# untitled.net
KiCad netlist of a schematic drawn in EAGLE
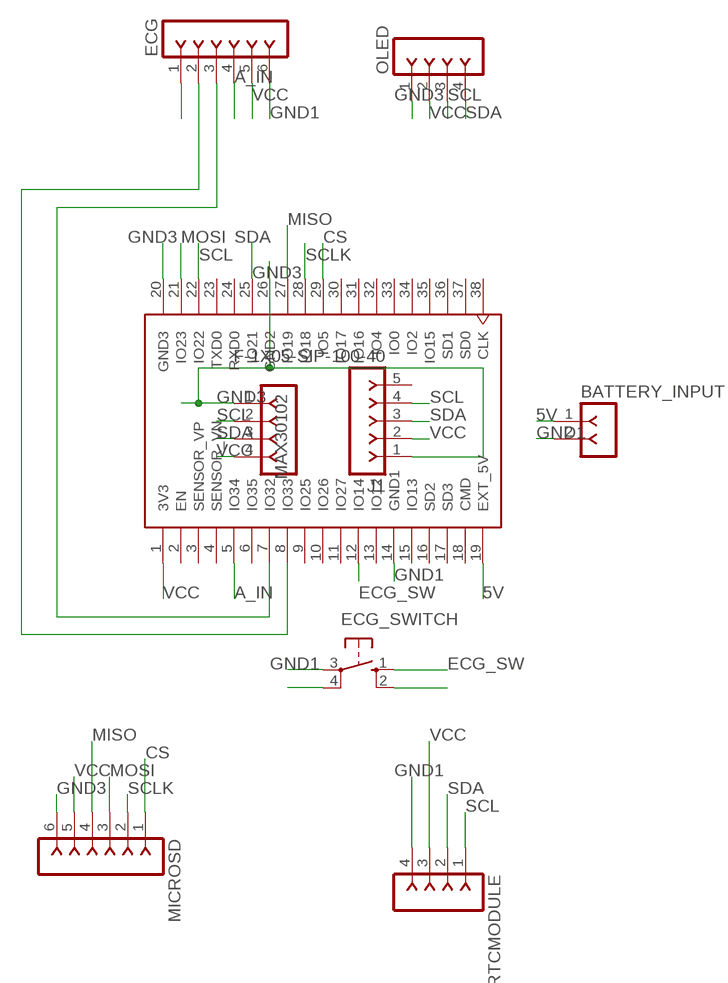
[diagram p0: schematic, sheet 1]

(export (version "E")
  (design (tool "Eeschema 10.0.6"))
  (components
    (comp (ref "BATTERY_INPUT")
      (value "F-1X02-SIP-100-40")
      (footprint "eagle-import:SIP-100-02-40")
      (libsource (lib "eagle-import") (part "F-1X02-SIP-100-40"))
    )
    (comp (ref "ECG")
      (value "F-1X06-SIP-100-40")
      (footprint "eagle-import:SIP-100-06-40")
      (libsource (lib "eagle-import") (part "F-1X06-SIP-100-40"))
    )
    (comp (ref "ECG_SWITCH")
      (value "10-XX")
      (footprint "eagle-import:B3F-10XX")
      (fields (field (name "MPN") "B3F-1000"))
      (libsource (lib "eagle-import") (part "10-XX"))
    )
    (comp (ref "J1")
      (value "F-1X05-SIP-100-40")
      (footprint "eagle-import:SIP-100-05-40")
      (libsource (lib "eagle-import") (part "F-1X05-SIP-100-40"))
    )
    (comp (ref "MAX30102")
      (value "F-1X04-SIP-100-40")
      (footprint "eagle-import:SIP-100-04-40")
      (libsource (lib "eagle-import") (part "F-1X04-SIP-100-40"))
    )
    (comp (ref "MICROSD")
      (value "F-1X06-SIP-100-40")
      (footprint "eagle-import:SIP-100-06-40")
      (libsource (lib "eagle-import") (part "F-1X06-SIP-100-40"))
    )
    (comp (ref "OLED")
      (value "F-1X04-SIP-100-40")
      (footprint "eagle-import:SIP-100-04-40")
      (libsource (lib "eagle-import") (part "F-1X04-SIP-100-40"))
    )
    (comp (ref "RTCMODULE")
      (value "F-1X04-SIP-100-40")
      (footprint "eagle-import:SIP-100-04-40")
      (libsource (lib "eagle-import") (part "F-1X04-SIP-100-40"))
    )
    (comp (ref "U1")
      (value "ESP32-DEVKITC-32D")
      (footprint "eagle-import:MODULE_ESP32-DEVKITC-32D")
      (fields (field (name "MF") "Espressif Systems"))
      (libsource (lib "eagle-import") (part "ESP32-DEVKITC-32D"))
    )
  )
  (nets
    (net (code "1") (name "/5V") (class "Default")
      (node (ref "BATTERY_INPUT") (pin "1") (pinfunction "1_1") (pintype "passive"))
      (node (ref "U1") (pin "19") (pinfunction "EXT_5V_19") (pintype "power_in"))
    )
    (net (code "2") (name "/A_IN") (class "Default")
      (node (ref "ECG") (pin "4") (pinfunction "4_4") (pintype "passive"))
      (node (ref "U1") (pin "5") (pinfunction "IO34_5") (pintype "bidirectional"))
    )
    (net (code "3") (name "/CS") (class "Default")
      (node (ref "MICROSD") (pin "1") (pinfunction "1_1") (pintype "passive"))
      (node (ref "U1") (pin "29") (pinfunction "IO5_29") (pintype "bidirectional"))
    )
    (net (code "4") (name "/ECG_SW") (class "Default")
      (node (ref "ECG_SWITCH") (pin "1") (pinfunction "S_1") (pintype "passive"))
      (node (ref "U1") (pin "12") (pinfunction "IO14_12") (pintype "bidirectional"))
    )
    (net (code "5") (name "/GND1") (class "Default")
      (node (ref "BATTERY_INPUT") (pin "2") (pinfunction "2_2") (pintype "passive"))
      (node (ref "ECG") (pin "6") (pinfunction "6_6") (pintype "passive"))
      (node (ref "ECG_SWITCH") (pin "3") (pinfunction "P_3") (pintype "passive"))
      (node (ref "RTCMODULE") (pin "4") (pinfunction "4_4") (pintype "passive"))
      (node (ref "U1") (pin "14") (pinfunction "GND1_14") (pintype "power_in"))
    )
    (net (code "6") (name "/GND3") (class "Default")
      (node (ref "J1") (pin "1") (pinfunction "1_1") (pintype "passive"))
      (node (ref "MAX30102") (pin "1") (pinfunction "1_1") (pintype "passive"))
      (node (ref "MICROSD") (pin "6") (pinfunction "6_6") (pintype "passive"))
      (node (ref "OLED") (pin "1") (pinfunction "1_1") (pintype "passive"))
      (node (ref "U1") (pin "20") (pinfunction "GND3_20") (pintype "power_in"))
      (node (ref "U1") (pin "26") (pinfunction "GND2_26") (pintype "power_in"))
    )
    (net (code "7") (name "/MISO") (class "Default")
      (node (ref "MICROSD") (pin "4") (pinfunction "4_4") (pintype "passive"))
      (node (ref "U1") (pin "27") (pinfunction "IO19_27") (pintype "bidirectional"))
    )
    (net (code "8") (name "/MOSI") (class "Default")
      (node (ref "MICROSD") (pin "3") (pinfunction "3_3") (pintype "passive"))
      (node (ref "U1") (pin "21") (pinfunction "IO23_21") (pintype "bidirectional"))
    )
    (net (code "9") (name "/SCL") (class "Default")
      (node (ref "J1") (pin "4") (pinfunction "4_4") (pintype "passive"))
      (node (ref "MAX30102") (pin "2") (pinfunction "2_2") (pintype "passive"))
      (node (ref "OLED") (pin "3") (pinfunction "3_3") (pintype "passive"))
      (node (ref "RTCMODULE") (pin "1") (pinfunction "1_1") (pintype "passive"))
      (node (ref "U1") (pin "22") (pinfunction "IO22_22") (pintype "bidirectional"))
    )
    (net (code "10") (name "/SCLK") (class "Default")
      (node (ref "MICROSD") (pin "2") (pinfunction "2_2") (pintype "passive"))
      (node (ref "U1") (pin "28") (pinfunction "IO18_28") (pintype "bidirectional"))
    )
    (net (code "11") (name "/SDA") (class "Default")
      (node (ref "J1") (pin "3") (pinfunction "3_3") (pintype "passive"))
      (node (ref "MAX30102") (pin "3") (pinfunction "3_3") (pintype "passive"))
      (node (ref "OLED") (pin "4") (pinfunction "4_4") (pintype "passive"))
      (node (ref "RTCMODULE") (pin "2") (pinfunction "2_2") (pintype "passive"))
      (node (ref "U1") (pin "25") (pinfunction "IO21_25") (pintype "bidirectional"))
    )
    (net (code "12") (name "/VCC") (class "Default")
      (node (ref "ECG") (pin "5") (pinfunction "5_5") (pintype "passive"))
      (node (ref "J1") (pin "2") (pinfunction "2_2") (pintype "passive"))
      (node (ref "MAX30102") (pin "4") (pinfunction "4_4") (pintype "passive"))
      (node (ref "MICROSD") (pin "5") (pinfunction "5_5") (pintype "passive"))
      (node (ref "OLED") (pin "2") (pinfunction "2_2") (pintype "passive"))
      (node (ref "RTCMODULE") (pin "3") (pinfunction "3_3") (pintype "passive"))
      (node (ref "U1") (pin "1") (pinfunction "3V3_1") (pintype "power_in"))
    )
    (net (code "13") (name "Net-(U1-IO32)") (class "Default")
      (node (ref "ECG") (pin "3") (pinfunction "3_3") (pintype "passive"))
      (node (ref "U1") (pin "7") (pinfunction "IO32_7") (pintype "bidirectional"))
    )
    (net (code "14") (name "Net-(U1-IO33)") (class "Default")
      (node (ref "ECG") (pin "2") (pinfunction "2_2") (pintype "passive"))
      (node (ref "U1") (pin "8") (pinfunction "IO33_8") (pintype "bidirectional"))
    )
    (net (code "15") (name "unconnected-(ECG-Pad1)") (class "Default")
      (node (ref "ECG") (pin "1") (pinfunction "1_1") (pintype "passive"))
    )
    (net (code "16") (name "unconnected-(ECG_SWITCH-P1-Pad4)") (class "Default")
      (node (ref "ECG_SWITCH") (pin "4") (pinfunction "P1_4") (pintype "passive"))
    )
    (net (code "17") (name "unconnected-(ECG_SWITCH-S1-Pad2)") (class "Default")
      (node (ref "ECG_SWITCH") (pin "2") (pinfunction "S1_2") (pintype "passive"))
    )
    (net (code "18") (name "unconnected-(J1-Pad5)") (class "Default")
      (node (ref "J1") (pin "5") (pinfunction "5_5") (pintype "passive"))
    )
    (net (code "19") (name "unconnected-(U1-CLK-Pad38)") (class "Default")
      (node (ref "U1") (pin "38") (pinfunction "CLK_38") (pintype "input"))
    )
    (net (code "20") (name "unconnected-(U1-CMD-Pad18)") (class "Default")
      (node (ref "U1") (pin "18") (pinfunction "CMD_18") (pintype "bidirectional"))
    )
    (net (code "21") (name "unconnected-(U1-EN-Pad2)") (class "Default")
      (node (ref "U1") (pin "2") (pinfunction "EN_2") (pintype "input"))
    )
    (net (code "22") (name "unconnected-(U1-IO0-Pad33)") (class "Default")
      (node (ref "U1") (pin "33") (pinfunction "IO0_33") (pintype "bidirectional"))
    )
    (net (code "23") (name "unconnected-(U1-IO2-Pad34)") (class "Default")
      (node (ref "U1") (pin "34") (pinfunction "IO2_34") (pintype "bidirectional"))
    )
    (net (code "24") (name "unconnected-(U1-IO4-Pad32)") (class "Default")
      (node (ref "U1") (pin "32") (pinfunction "IO4_32") (pintype "bidirectional"))
    )
    (net (code "25") (name "unconnected-(U1-IO12-Pad13)") (class "Default")
      (node (ref "U1") (pin "13") (pinfunction "IO12_13") (pintype "bidirectional"))
    )
    (net (code "26") (name "unconnected-(U1-IO13-Pad15)") (class "Default")
      (node (ref "U1") (pin "15") (pinfunction "IO13_15") (pintype "bidirectional"))
    )
    (net (code "27") (name "unconnected-(U1-IO15-Pad35)") (class "Default")
      (node (ref "U1") (pin "35") (pinfunction "IO15_35") (pintype "bidirectional"))
    )
    (net (code "28") (name "unconnected-(U1-IO16-Pad31)") (class "Default")
      (node (ref "U1") (pin "31") (pinfunction "IO16_31") (pintype "bidirectional"))
    )
    (net (code "29") (name "unconnected-(U1-IO17-Pad30)") (class "Default")
      (node (ref "U1") (pin "30") (pinfunction "IO17_30") (pintype "bidirectional"))
    )
    (net (code "30") (name "unconnected-(U1-IO25-Pad9)") (class "Default")
      (node (ref "U1") (pin "9") (pinfunction "IO25_9") (pintype "bidirectional"))
    )
    (net (code "31") (name "unconnected-(U1-IO26-Pad10)") (class "Default")
      (node (ref "U1") (pin "10") (pinfunction "IO26_10") (pintype "bidirectional"))
    )
    (net (code "32") (name "unconnected-(U1-IO27-Pad11)") (class "Default")
      (node (ref "U1") (pin "11") (pinfunction "IO27_11") (pintype "bidirectional"))
    )
    (net (code "33") (name "unconnected-(U1-IO35-Pad6)") (class "Default")
      (node (ref "U1") (pin "6") (pinfunction "IO35_6") (pintype "bidirectional"))
    )
    (net (code "34") (name "unconnected-(U1-RXD0-Pad24)") (class "Default")
      (node (ref "U1") (pin "24") (pinfunction "RXD0_24") (pintype "input"))
    )
    (net (code "35") (name "unconnected-(U1-SD0-Pad37)") (class "Default")
      (node (ref "U1") (pin "37") (pinfunction "SD0_37") (pintype "bidirectional"))
    )
    (net (code "36") (name "unconnected-(U1-SD1-Pad36)") (class "Default")
      (node (ref "U1") (pin "36") (pinfunction "SD1_36") (pintype "bidirectional"))
    )
    (net (code "37") (name "unconnected-(U1-SD2-Pad16)") (class "Default")
      (node (ref "U1") (pin "16") (pinfunction "SD2_16") (pintype "bidirectional"))
    )
    (net (code "38") (name "unconnected-(U1-SD3-Pad17)") (class "Default")
      (node (ref "U1") (pin "17") (pinfunction "SD3_17") (pintype "bidirectional"))
    )
    (net (code "39") (name "unconnected-(U1-SENSOR_VN-Pad4)") (class "Default")
      (node (ref "U1") (pin "4") (pinfunction "SENSOR_VN_4") (pintype "input"))
    )
    (net (code "40") (name "unconnected-(U1-SENSOR_VP-Pad3)") (class "Default")
      (node (ref "U1") (pin "3") (pinfunction "SENSOR_VP_3") (pintype "input"))
    )
    (net (code "41") (name "unconnected-(U1-TXD0-Pad23)") (class "Default")
      (node (ref "U1") (pin "23") (pinfunction "TXD0_23") (pintype "output"))
    )
  )
)
